# 08_AFBUS.net
KiCad netlist of a schematic drawn in Altium Designer
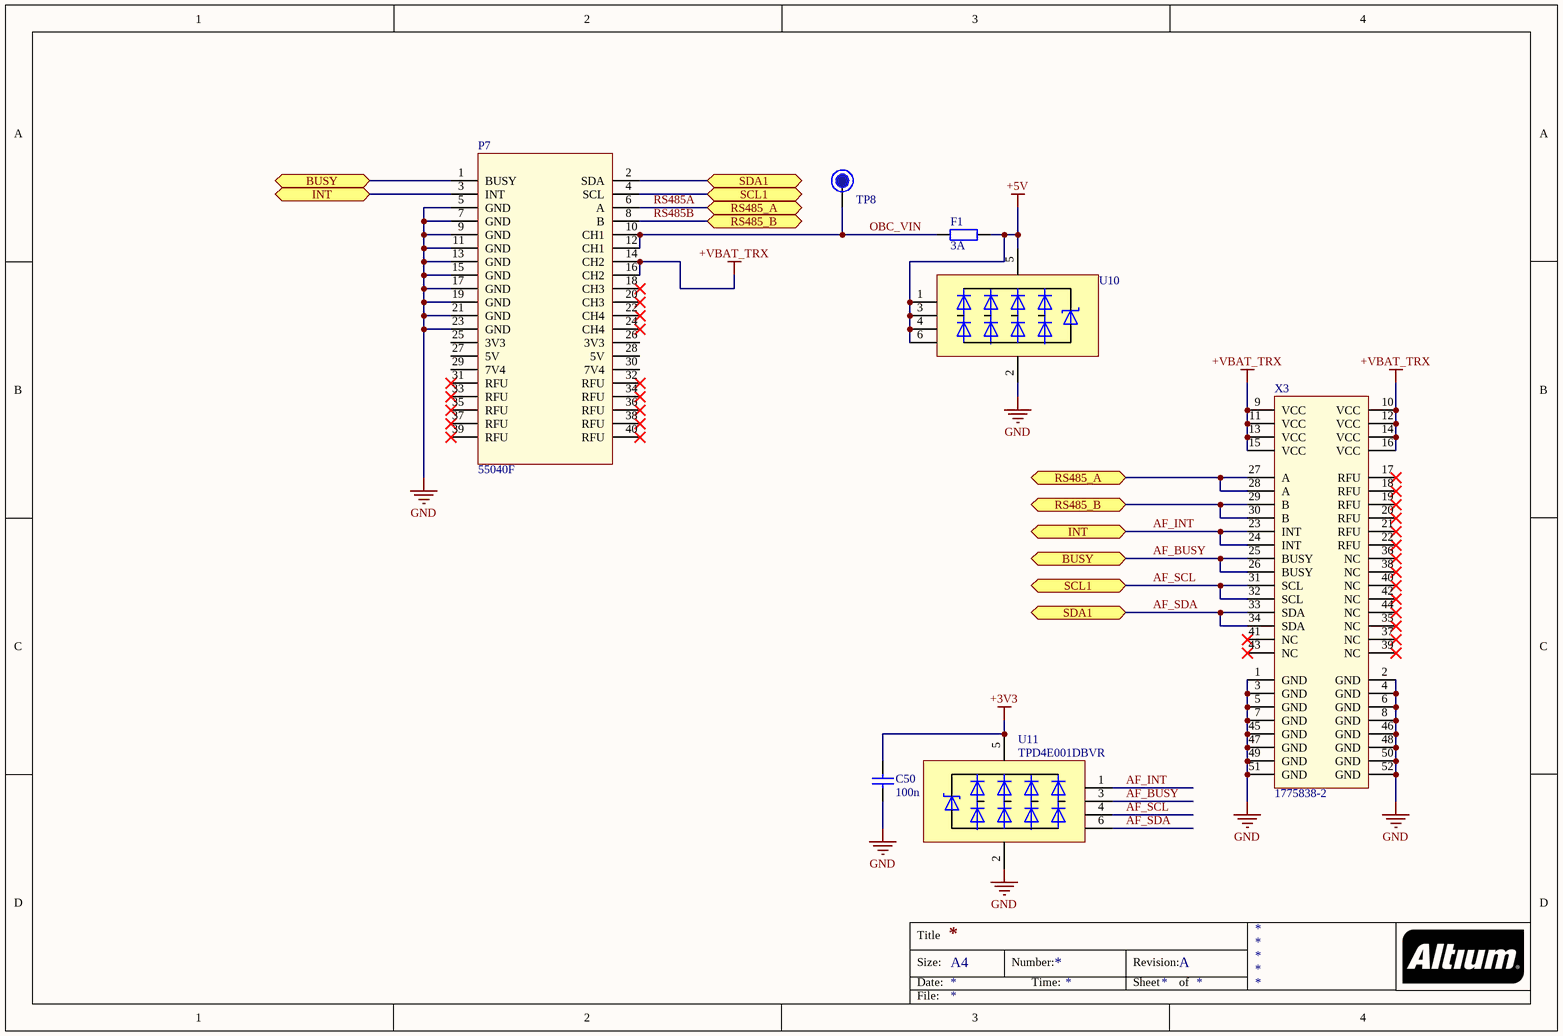
[diagram p0: 08_AFBUS.SchDoc]

(export (version "E")
  (design (tool "Eeschema 10.0.6"))
  (components
    (comp (ref "C50")
      (value "100n")
      (footprint "C0603_IPC_HD")
      (description "CAP CER 0.1UF 16V X7R 0603")
      (fields
        (field (name "MANUFACTURER") "Samsung Electro-Mechanics")
        (field (name "MANUFACTURER PART NUMBER") "CL10B104KO8NNNC")
      )
      (libsource (lib "alfasat_lib") (part "CL10B104KO8NNNC"))
    )
    (comp (ref "F1")
      (value "3A")
      (footprint "F0603_IPC_MD")
      (description "FUSE BRD MNT 3A 32VAC 63VDC 0603")
      (fields (field (name "MANUFACTURER") "Bel Fuse Inc.") (field (name "MANUFACTURER PART NUMBER") "C2Q3"))
      (libsource (lib "alfasat_lib") (part "C2Q3"))
    )
    (comp (ref "P7")
      (value "55040F")
      (footprint "HEADER_40PIN_12MM2")
      (description "CONN HEADER R/A 40POS 2.54MM")
      (fields (field (name "MANUFACTURER") "On Shore Technology Inc."))
      (libsource (lib "alfasat_lib") (part "ALFASAT_BIC"))
    )
    (comp (ref "TP8")
      (value "VIN")
      (footprint "TestPoint_1M5")
      (description "Test Point")
      (libsource (lib "alfasat_lib") (part "TP"))
    )
    (comp (ref "U10")
      (value "TPD4E001DBVR")
      (footprint "SOT23-6")
      (description "4x TVS DIODE 5.5V SOT23-6")
      (fields (field (name "MANUFACTURER") "TI"))
      (libsource (lib "") (part "TPD4E001DBVR_1"))
    )
    (comp (ref "U11")
      (value "TPD4E001DBVR")
      (footprint "SOT23-6")
      (description "4x TVS DIODE 5.5V SOT23-6")
      (fields (field (name "MANUFACTURER") "TI"))
      (libsource (lib "alfasat_lib") (part "TPD4E001DBVR"))
    )
    (comp (ref "X3")
      (value "1775838-2")
      (footprint "1775838-2")
      (description "CONN PCI EXP MINI FEMALE 52POS")
      (fields (field (name "MANUFACTURER") "TE Connectivity AMP Connectors"))
      (libsource (lib "alfasat_parts_lib") (part "ALAFASAT_TRX_PCI"))
    )
  )
  (nets
    (net (code "1") (name "+3V3") (class "Default")
      (node (ref "C50") (pin "2") (pinfunction "2_2") (pintype "passive"))
      (node (ref "U11") (pin "5") (pinfunction "VCC_5") (pintype "power_in"))
    )
    (net (code "2") (name "+5V") (class "Default")
      (node (ref "F1") (pin "2") (pinfunction "2_2") (pintype "passive"))
      (node (ref "U10") (pin "1") (pinfunction "IO1_1") (pintype "passive"))
      (node (ref "U10") (pin "3") (pinfunction "IO2_3") (pintype "passive"))
      (node (ref "U10") (pin "4") (pinfunction "IO3_4") (pintype "passive"))
      (node (ref "U10") (pin "5") (pinfunction "VCC_5") (pintype "power_in"))
      (node (ref "U10") (pin "6") (pinfunction "IO4_6") (pintype "passive"))
    )
    (net (code "3") (name "+VBAT_TRX") (class "Default")
      (node (ref "P7") (pin "14") (pinfunction "CH2_14") (pintype "passive"))
      (node (ref "P7") (pin "16") (pinfunction "CH2_16") (pintype "passive"))
      (node (ref "X3") (pin "10") (pinfunction "VCC_10") (pintype "passive"))
      (node (ref "X3") (pin "11") (pinfunction "VCC_11") (pintype "passive"))
      (node (ref "X3") (pin "12") (pinfunction "VCC_12") (pintype "passive"))
      (node (ref "X3") (pin "13") (pinfunction "VCC_13") (pintype "passive"))
      (node (ref "X3") (pin "14") (pinfunction "VCC_14") (pintype "passive"))
      (node (ref "X3") (pin "15") (pinfunction "VCC_15") (pintype "passive"))
      (node (ref "X3") (pin "16") (pinfunction "VCC_16") (pintype "passive"))
      (node (ref "X3") (pin "9") (pinfunction "VCC_9") (pintype "passive"))
    )
    (net (code "4") (name "/AF_BUSY") (class "Default")
      (node (ref "P7") (pin "1") (pinfunction "BUSY_1") (pintype "passive"))
      (node (ref "U11") (pin "3") (pinfunction "IO2_3") (pintype "passive"))
      (node (ref "X3") (pin "25") (pinfunction "BUSY_25") (pintype "passive"))
      (node (ref "X3") (pin "26") (pinfunction "BUSY_26") (pintype "passive"))
    )
    (net (code "5") (name "/AF_INT") (class "Default")
      (node (ref "P7") (pin "3") (pinfunction "INT_3") (pintype "passive"))
      (node (ref "U11") (pin "1") (pinfunction "IO1_1") (pintype "passive"))
      (node (ref "X3") (pin "23") (pinfunction "INT_23") (pintype "passive"))
      (node (ref "X3") (pin "24") (pinfunction "INT_24") (pintype "passive"))
    )
    (net (code "6") (name "/AF_SCL") (class "Default")
      (node (ref "P7") (pin "4") (pinfunction "SCL_4") (pintype "passive"))
      (node (ref "U11") (pin "4") (pinfunction "IO3_4") (pintype "passive"))
      (node (ref "X3") (pin "31") (pinfunction "SCL_31") (pintype "passive"))
      (node (ref "X3") (pin "32") (pinfunction "SCL_32") (pintype "passive"))
    )
    (net (code "7") (name "/AF_SDA") (class "Default")
      (node (ref "P7") (pin "2") (pinfunction "SDA_2") (pintype "passive"))
      (node (ref "U11") (pin "6") (pinfunction "IO4_6") (pintype "passive"))
      (node (ref "X3") (pin "33") (pinfunction "SDA_33") (pintype "passive"))
      (node (ref "X3") (pin "34") (pinfunction "SDA_34") (pintype "passive"))
    )
    (net (code "8") (name "/OBC_VIN") (class "Default")
      (node (ref "F1") (pin "1") (pinfunction "1_1") (pintype "passive"))
      (node (ref "P7") (pin "10") (pinfunction "CH1_10") (pintype "passive"))
      (node (ref "P7") (pin "12") (pinfunction "CH1_12") (pintype "passive"))
      (node (ref "TP8") (pin "0") (pinfunction "0_0") (pintype "passive"))
    )
    (net (code "9") (name "/RS485A") (class "Default")
      (node (ref "P7") (pin "6") (pinfunction "A_6") (pintype "passive"))
      (node (ref "X3") (pin "27") (pinfunction "A_27") (pintype "passive"))
      (node (ref "X3") (pin "28") (pinfunction "A_28") (pintype "passive"))
    )
    (net (code "10") (name "/RS485B") (class "Default")
      (node (ref "P7") (pin "8") (pinfunction "B_8") (pintype "passive"))
      (node (ref "X3") (pin "29") (pinfunction "B_29") (pintype "passive"))
      (node (ref "X3") (pin "30") (pinfunction "B_30") (pintype "passive"))
    )
    (net (code "11") (name "GND") (class "Default")
      (node (ref "C50") (pin "1") (pinfunction "1_1") (pintype "passive"))
      (node (ref "P7") (pin "11") (pinfunction "GND_11") (pintype "passive"))
      (node (ref "P7") (pin "13") (pinfunction "GND_13") (pintype "passive"))
      (node (ref "P7") (pin "15") (pinfunction "GND_15") (pintype "passive"))
      (node (ref "P7") (pin "17") (pinfunction "GND_17") (pintype "passive"))
      (node (ref "P7") (pin "19") (pinfunction "GND_19") (pintype "passive"))
      (node (ref "P7") (pin "21") (pinfunction "GND_21") (pintype "passive"))
      (node (ref "P7") (pin "23") (pinfunction "GND_23") (pintype "passive"))
      (node (ref "P7") (pin "5") (pinfunction "GND_5") (pintype "passive"))
      (node (ref "P7") (pin "7") (pinfunction "GND_7") (pintype "passive"))
      (node (ref "P7") (pin "9") (pinfunction "GND_9") (pintype "passive"))
      (node (ref "U10") (pin "2") (pinfunction "GND_2") (pintype "power_in"))
      (node (ref "U11") (pin "2") (pinfunction "GND_2") (pintype "power_in"))
      (node (ref "X3") (pin "1") (pinfunction "GND_1") (pintype "passive"))
      (node (ref "X3") (pin "2") (pinfunction "GND_2") (pintype "passive"))
      (node (ref "X3") (pin "3") (pinfunction "GND_3") (pintype "passive"))
      (node (ref "X3") (pin "4") (pinfunction "GND_4") (pintype "passive"))
      (node (ref "X3") (pin "45") (pinfunction "GND_45") (pintype "passive"))
      (node (ref "X3") (pin "46") (pinfunction "GND_46") (pintype "passive"))
      (node (ref "X3") (pin "47") (pinfunction "GND_47") (pintype "passive"))
      (node (ref "X3") (pin "48") (pinfunction "GND_48") (pintype "passive"))
      (node (ref "X3") (pin "49") (pinfunction "GND_49") (pintype "passive"))
      (node (ref "X3") (pin "5") (pinfunction "GND_5") (pintype "passive"))
      (node (ref "X3") (pin "50") (pinfunction "GND_50") (pintype "passive"))
      (node (ref "X3") (pin "51") (pinfunction "GND_51") (pintype "passive"))
      (node (ref "X3") (pin "52") (pinfunction "GND_52") (pintype "passive"))
      (node (ref "X3") (pin "6") (pinfunction "GND_6") (pintype "passive"))
      (node (ref "X3") (pin "7") (pinfunction "GND_7") (pintype "passive"))
      (node (ref "X3") (pin "8") (pinfunction "GND_8") (pintype "passive"))
    )
    (net (code "12") (name "unconnected-(P7-3V3-Pad25)") (class "Default")
      (node (ref "P7") (pin "25") (pinfunction "3V3_25") (pintype "passive"))
    )
    (net (code "13") (name "unconnected-(P7-3V3-Pad26)") (class "Default")
      (node (ref "P7") (pin "26") (pinfunction "3V3_26") (pintype "passive"))
    )
    (net (code "14") (name "unconnected-(P7-5V-Pad27)") (class "Default")
      (node (ref "P7") (pin "27") (pinfunction "5V_27") (pintype "passive"))
    )
    (net (code "15") (name "unconnected-(P7-5V-Pad28)") (class "Default")
      (node (ref "P7") (pin "28") (pinfunction "5V_28") (pintype "passive"))
    )
    (net (code "16") (name "unconnected-(P7-7V4-Pad29)") (class "Default")
      (node (ref "P7") (pin "29") (pinfunction "7V4_29") (pintype "passive"))
    )
    (net (code "17") (name "unconnected-(P7-7V4-Pad30)") (class "Default")
      (node (ref "P7") (pin "30") (pinfunction "7V4_30") (pintype "passive"))
    )
    (net (code "18") (name "unconnected-(P7-CH3-Pad18)") (class "Default")
      (node (ref "P7") (pin "18") (pinfunction "CH3_18") (pintype "passive+no_connect"))
    )
    (net (code "19") (name "unconnected-(P7-CH3-Pad20)") (class "Default")
      (node (ref "P7") (pin "20") (pinfunction "CH3_20") (pintype "passive+no_connect"))
    )
    (net (code "20") (name "unconnected-(P7-CH4-Pad22)") (class "Default")
      (node (ref "P7") (pin "22") (pinfunction "CH4_22") (pintype "passive+no_connect"))
    )
    (net (code "21") (name "unconnected-(P7-CH4-Pad24)") (class "Default")
      (node (ref "P7") (pin "24") (pinfunction "CH4_24") (pintype "passive+no_connect"))
    )
    (net (code "22") (name "unconnected-(P7-RFU-Pad31)") (class "Default")
      (node (ref "P7") (pin "31") (pinfunction "RFU_31") (pintype "passive+no_connect"))
    )
    (net (code "23") (name "unconnected-(P7-RFU-Pad32)") (class "Default")
      (node (ref "P7") (pin "32") (pinfunction "RFU_32") (pintype "passive+no_connect"))
    )
    (net (code "24") (name "unconnected-(P7-RFU-Pad33)") (class "Default")
      (node (ref "P7") (pin "33") (pinfunction "RFU_33") (pintype "passive+no_connect"))
    )
    (net (code "25") (name "unconnected-(P7-RFU-Pad34)") (class "Default")
      (node (ref "P7") (pin "34") (pinfunction "RFU_34") (pintype "passive+no_connect"))
    )
    (net (code "26") (name "unconnected-(P7-RFU-Pad35)") (class "Default")
      (node (ref "P7") (pin "35") (pinfunction "RFU_35") (pintype "passive+no_connect"))
    )
    (net (code "27") (name "unconnected-(P7-RFU-Pad36)") (class "Default")
      (node (ref "P7") (pin "36") (pinfunction "RFU_36") (pintype "passive+no_connect"))
    )
    (net (code "28") (name "unconnected-(P7-RFU-Pad37)") (class "Default")
      (node (ref "P7") (pin "37") (pinfunction "RFU_37") (pintype "passive+no_connect"))
    )
    (net (code "29") (name "unconnected-(P7-RFU-Pad38)") (class "Default")
      (node (ref "P7") (pin "38") (pinfunction "RFU_38") (pintype "passive+no_connect"))
    )
    (net (code "30") (name "unconnected-(P7-RFU-Pad39)") (class "Default")
      (node (ref "P7") (pin "39") (pinfunction "RFU_39") (pintype "passive+no_connect"))
    )
    (net (code "31") (name "unconnected-(P7-RFU-Pad40)") (class "Default")
      (node (ref "P7") (pin "40") (pinfunction "RFU_40") (pintype "passive+no_connect"))
    )
    (net (code "32") (name "unconnected-(X3-NC-Pad35)") (class "Default")
      (node (ref "X3") (pin "35") (pinfunction "NC_35") (pintype "passive+no_connect"))
    )
    (net (code "33") (name "unconnected-(X3-NC-Pad36)") (class "Default")
      (node (ref "X3") (pin "36") (pinfunction "NC_36") (pintype "passive+no_connect"))
    )
    (net (code "34") (name "unconnected-(X3-NC-Pad37)") (class "Default")
      (node (ref "X3") (pin "37") (pinfunction "NC_37") (pintype "passive+no_connect"))
    )
    (net (code "35") (name "unconnected-(X3-NC-Pad38)") (class "Default")
      (node (ref "X3") (pin "38") (pinfunction "NC_38") (pintype "passive+no_connect"))
    )
    (net (code "36") (name "unconnected-(X3-NC-Pad39)") (class "Default")
      (node (ref "X3") (pin "39") (pinfunction "NC_39") (pintype "passive+no_connect"))
    )
    (net (code "37") (name "unconnected-(X3-NC-Pad40)") (class "Default")
      (node (ref "X3") (pin "40") (pinfunction "NC_40") (pintype "passive+no_connect"))
    )
    (net (code "38") (name "unconnected-(X3-NC-Pad41)") (class "Default")
      (node (ref "X3") (pin "41") (pinfunction "NC_41") (pintype "passive+no_connect"))
    )
    (net (code "39") (name "unconnected-(X3-NC-Pad42)") (class "Default")
      (node (ref "X3") (pin "42") (pinfunction "NC_42") (pintype "passive+no_connect"))
    )
    (net (code "40") (name "unconnected-(X3-NC-Pad43)") (class "Default")
      (node (ref "X3") (pin "43") (pinfunction "NC_43") (pintype "passive+no_connect"))
    )
    (net (code "41") (name "unconnected-(X3-NC-Pad44)") (class "Default")
      (node (ref "X3") (pin "44") (pinfunction "NC_44") (pintype "passive+no_connect"))
    )
    (net (code "42") (name "unconnected-(X3-RFU-Pad17)") (class "Default")
      (node (ref "X3") (pin "17") (pinfunction "RFU_17") (pintype "passive+no_connect"))
    )
    (net (code "43") (name "unconnected-(X3-RFU-Pad18)") (class "Default")
      (node (ref "X3") (pin "18") (pinfunction "RFU_18") (pintype "passive+no_connect"))
    )
    (net (code "44") (name "unconnected-(X3-RFU-Pad19)") (class "Default")
      (node (ref "X3") (pin "19") (pinfunction "RFU_19") (pintype "passive+no_connect"))
    )
    (net (code "45") (name "unconnected-(X3-RFU-Pad20)") (class "Default")
      (node (ref "X3") (pin "20") (pinfunction "RFU_20") (pintype "passive+no_connect"))
    )
    (net (code "46") (name "unconnected-(X3-RFU-Pad21)") (class "Default")
      (node (ref "X3") (pin "21") (pinfunction "RFU_21") (pintype "passive+no_connect"))
    )
    (net (code "47") (name "unconnected-(X3-RFU-Pad22)") (class "Default")
      (node (ref "X3") (pin "22") (pinfunction "RFU_22") (pintype "passive+no_connect"))
    )
  )
)
